# synthesizer-IF-Si4112.net
KiCad netlist of a schematic drawn in EAGLE
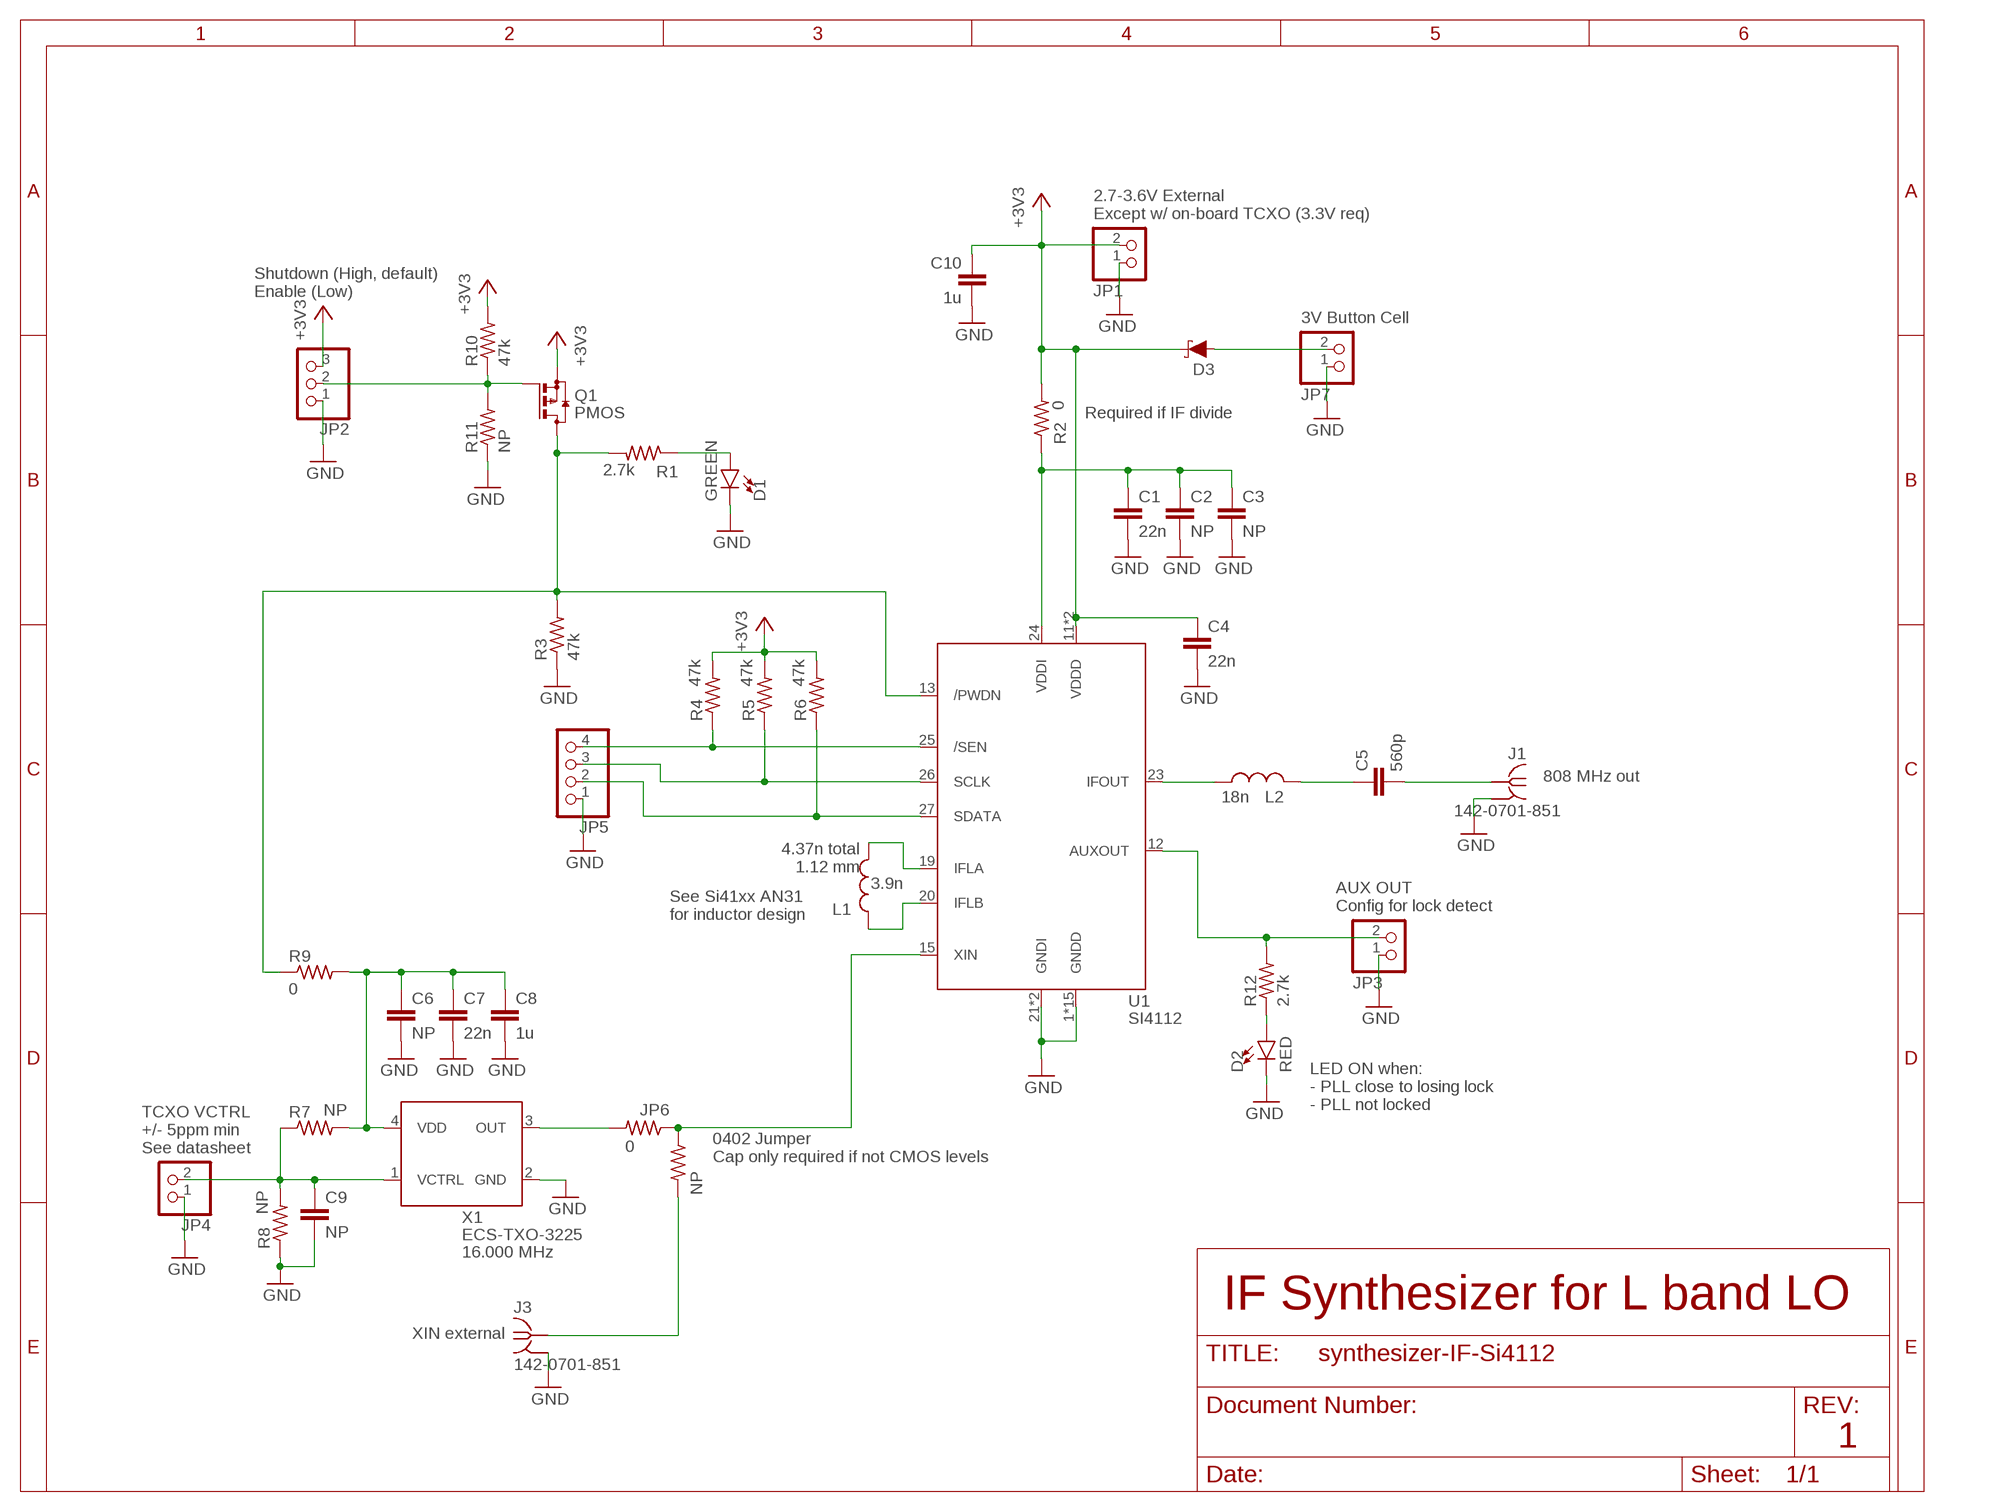
[diagram p0: schematic, sheet 1]

(export (version "E")
  (design (tool "Eeschema 10.0.6"))
  (components
    (comp (ref "C1")
      (value "22n")
      (footprint "eagle-import:.0603-B-NOSILK")
      (libsource (lib "eagle-import") (part "C-EU0603-B-NOSILK"))
    )
    (comp (ref "C2")
      (value "NP")
      (footprint "eagle-import:.0603-B-NOSILK")
      (libsource (lib "eagle-import") (part "C-EU0603-B-NOSILK"))
    )
    (comp (ref "C3")
      (value "NP")
      (footprint "eagle-import:.0603-B-NOSILK")
      (libsource (lib "eagle-import") (part "C-EU0603-B-NOSILK"))
    )
    (comp (ref "C4")
      (value "22n")
      (footprint "eagle-import:.0603-B-NOSILK")
      (libsource (lib "eagle-import") (part "C-EU0603-B-NOSILK"))
    )
    (comp (ref "C5")
      (value "560p")
      (footprint "eagle-import:.0402-B-NOSILK")
      (libsource (lib "eagle-import") (part "C-EU0402-B-NOSILK"))
    )
    (comp (ref "C6")
      (value "NP")
      (footprint "eagle-import:.0603-B-NOSILK")
      (libsource (lib "eagle-import") (part "C-EU0603-B-NOSILK"))
    )
    (comp (ref "C7")
      (value "22n")
      (footprint "eagle-import:.0603-B-NOSILK")
      (libsource (lib "eagle-import") (part "C-EU0603-B-NOSILK"))
    )
    (comp (ref "C8")
      (value "1u")
      (footprint "eagle-import:.0603-B-NOSILK")
      (libsource (lib "eagle-import") (part "C-EU0603-B-NOSILK"))
    )
    (comp (ref "C9")
      (value "NP")
      (footprint "eagle-import:.0603-B-NOSILK")
      (libsource (lib "eagle-import") (part "C-EU0603-B-NOSILK"))
    )
    (comp (ref "C10")
      (value "1u")
      (footprint "eagle-import:.0603-B-NOSILK")
      (libsource (lib "eagle-import") (part "C-EU0603-B-NOSILK"))
    )
    (comp (ref "D1")
      (value "GREEN")
      (footprint "eagle-import:LED-0603")
      (libsource (lib "eagle-import") (part "LED-GREEN0603"))
    )
    (comp (ref "D2")
      (value "RED")
      (footprint "eagle-import:LED-0603")
      (libsource (lib "eagle-import") (part "LED-GREEN0603"))
    )
    (comp (ref "D3")
      (value "120mA/40V/370mV")
      (footprint "eagle-import:SOD-523")
      (libsource (lib "eagle-import") (part "DIODE-SCHOTTKY-RB751S40"))
    )
    (comp (ref "J1")
      (value "142-0701-851")
      (footprint "eagle-import:142-0701-851")
      (libsource (lib "eagle-import") (part "142-0701-851"))
    )
    (comp (ref "J3")
      (value "142-0701-851")
      (footprint "eagle-import:142-0701-851")
      (libsource (lib "eagle-import") (part "142-0701-851"))
    )
    (comp (ref "JP1")
      (value "PINHD-1X2")
      (footprint "eagle-import:1X02")
      (libsource (lib "eagle-import") (part "PINHD-1X2"))
    )
    (comp (ref "JP2")
      (value "PINHD-1X3")
      (footprint "eagle-import:1X03")
      (libsource (lib "eagle-import") (part "PINHD-1X3"))
    )
    (comp (ref "JP3")
      (value "PINHD-1X2")
      (footprint "eagle-import:1X02")
      (libsource (lib "eagle-import") (part "PINHD-1X2"))
    )
    (comp (ref "JP4")
      (value "PINHD-1X2")
      (footprint "eagle-import:1X02")
      (libsource (lib "eagle-import") (part "PINHD-1X2"))
    )
    (comp (ref "JP5")
      (value "PINHD-1X4")
      (footprint "eagle-import:1X04")
      (libsource (lib "eagle-import") (part "PINHD-1X4"))
    )
    (comp (ref "JP6")
      (value "0")
      (footprint "eagle-import:.0402-B-NOSILK")
      (libsource (lib "eagle-import") (part "R-US_0402-B-NOSILK"))
    )
    (comp (ref "JP7")
      (value "PINHD-1X2")
      (footprint "eagle-import:1X02")
      (libsource (lib "eagle-import") (part "PINHD-1X2"))
    )
    (comp (ref "L1")
      (value "3.9n")
      (footprint "eagle-import:.0402-C-NOSILK")
      (libsource (lib "eagle-import") (part "L-US0402-C-NOSILK"))
    )
    (comp (ref "L2")
      (value "18n")
      (footprint "eagle-import:.0402-B-NOSILK")
      (libsource (lib "eagle-import") (part "L-US0402-B-NOSILK"))
    )
    (comp (ref "Q1")
      (value "PMOS")
      (footprint "eagle-import:SOT23")
      (libsource (lib "eagle-import") (part "BSS84"))
    )
    (comp (ref "R1")
      (value "2.7k")
      (footprint "eagle-import:.0603-B-NOSILK")
      (libsource (lib "eagle-import") (part "R-US_0603-B-NOSILK"))
    )
    (comp (ref "R2")
      (value "0")
      (footprint "eagle-import:.0603-B-NOSILK")
      (libsource (lib "eagle-import") (part "R-US_0603-B-NOSILK"))
    )
    (comp (ref "R3")
      (value "47k")
      (footprint "eagle-import:.0402-B-NOSILK")
      (libsource (lib "eagle-import") (part "R-US_0402-B-NOSILK"))
    )
    (comp (ref "R4")
      (value "47k")
      (footprint "eagle-import:.0402-B-NOSILK")
      (libsource (lib "eagle-import") (part "R-US_0402-B-NOSILK"))
    )
    (comp (ref "R5")
      (value "47k")
      (footprint "eagle-import:.0402-B-NOSILK")
      (libsource (lib "eagle-import") (part "R-US_0402-B-NOSILK"))
    )
    (comp (ref "R6")
      (value "47k")
      (footprint "eagle-import:.0402-B-NOSILK")
      (libsource (lib "eagle-import") (part "R-US_0402-B-NOSILK"))
    )
    (comp (ref "R7")
      (value "NP")
      (footprint "eagle-import:.0603-B-NOSILK")
      (libsource (lib "eagle-import") (part "R-US_0603-B-NOSILK"))
    )
    (comp (ref "R8")
      (value "NP")
      (footprint "eagle-import:.0603-B-NOSILK")
      (libsource (lib "eagle-import") (part "R-US_0603-B-NOSILK"))
    )
    (comp (ref "R9")
      (value "0")
      (footprint "eagle-import:.0603-B-NOSILK")
      (libsource (lib "eagle-import") (part "R-US_0603-B-NOSILK"))
    )
    (comp (ref "R10")
      (value "47k")
      (footprint "eagle-import:.0402-B-NOSILK")
      (libsource (lib "eagle-import") (part "R-US_0402-B-NOSILK"))
    )
    (comp (ref "R11")
      (value "NP")
      (footprint "eagle-import:.0402-B-NOSILK")
      (libsource (lib "eagle-import") (part "R-US_0402-B-NOSILK"))
    )
    (comp (ref "R12")
      (value "2.7k")
      (footprint "eagle-import:.0603-B-NOSILK")
      (libsource (lib "eagle-import") (part "R-US_0603-B-NOSILK"))
    )
    (comp (ref "R99")
      (value "NP")
      (footprint "eagle-import:.0402-B-NOSILK")
      (libsource (lib "eagle-import") (part "R-US_0402-B-NOSILK"))
    )
    (comp (ref "U1")
      (value "SI4112")
      (footprint "eagle-import:QFN28-5X5-WITH-CENTER-PAD")
      (libsource (lib "eagle-import") (part "SI4112"))
    )
    (comp (ref "X1")
      (value "ECS-TXO-3225")
      (footprint "eagle-import:3.2X2.5")
      (libsource (lib "eagle-import") (part "ECS-TXO-3225"))
    )
  )
  (nets
    (net (code "1") (name "+3V3") (class "Default")
      (node (ref "C10") (pin "1") (pinfunction "1_1") (pintype "passive"))
      (node (ref "C4") (pin "1") (pinfunction "1_1") (pintype "passive"))
      (node (ref "D3") (pin "C") (pinfunction "C_C") (pintype "passive"))
      (node (ref "JP1") (pin "2") (pinfunction "2_2") (pintype "passive"))
      (node (ref "JP2") (pin "3") (pinfunction "3_3") (pintype "passive"))
      (node (ref "Q1") (pin "2") (pinfunction "S_2") (pintype "passive"))
      (node (ref "R10") (pin "2") (pinfunction "2_2") (pintype "passive"))
      (node (ref "R2") (pin "2") (pinfunction "2_2") (pintype "passive"))
      (node (ref "R4") (pin "2") (pinfunction "2_2") (pintype "passive"))
      (node (ref "R5") (pin "2") (pinfunction "2_2") (pintype "passive"))
      (node (ref "R6") (pin "2") (pinfunction "2_2") (pintype "passive"))
      (node (ref "U1") (pin "11") (pinfunction "VDDD_11") (pintype "power_in"))
      (node (ref "U1") (pin "17") (pinfunction "VDDD_17") (pintype "power_in"))
    )
    (net (code "2") (name "GND") (class "Default")
      (node (ref "C1") (pin "2") (pinfunction "2_2") (pintype "passive"))
      (node (ref "C10") (pin "2") (pinfunction "2_2") (pintype "passive"))
      (node (ref "C2") (pin "2") (pinfunction "2_2") (pintype "passive"))
      (node (ref "C3") (pin "2") (pinfunction "2_2") (pintype "passive"))
      (node (ref "C4") (pin "2") (pinfunction "2_2") (pintype "passive"))
      (node (ref "C6") (pin "2") (pinfunction "2_2") (pintype "passive"))
      (node (ref "C7") (pin "2") (pinfunction "2_2") (pintype "passive"))
      (node (ref "C8") (pin "2") (pinfunction "2_2") (pintype "passive"))
      (node (ref "C9") (pin "2") (pinfunction "2_2") (pintype "passive"))
      (node (ref "D1") (pin "C") (pinfunction "C_C") (pintype "passive"))
      (node (ref "D2") (pin "C") (pinfunction "C_C") (pintype "passive"))
      (node (ref "J1") (pin "GND1") (pinfunction "GND_GND1") (pintype "bidirectional"))
      (node (ref "J1") (pin "GND2") (pinfunction "GND_GND2") (pintype "bidirectional"))
      (node (ref "J1") (pin "GND3") (pinfunction "GND_GND3") (pintype "bidirectional"))
      (node (ref "J1") (pin "GND4") (pinfunction "GND_GND4") (pintype "bidirectional"))
      (node (ref "J3") (pin "GND1") (pinfunction "GND_GND1") (pintype "bidirectional"))
      (node (ref "J3") (pin "GND2") (pinfunction "GND_GND2") (pintype "bidirectional"))
      (node (ref "J3") (pin "GND3") (pinfunction "GND_GND3") (pintype "bidirectional"))
      (node (ref "J3") (pin "GND4") (pinfunction "GND_GND4") (pintype "bidirectional"))
      (node (ref "JP1") (pin "1") (pinfunction "1_1") (pintype "passive"))
      (node (ref "JP2") (pin "1") (pinfunction "1_1") (pintype "passive"))
      (node (ref "JP3") (pin "1") (pinfunction "1_1") (pintype "passive"))
      (node (ref "JP4") (pin "1") (pinfunction "1_1") (pintype "passive"))
      (node (ref "JP5") (pin "1") (pinfunction "1_1") (pintype "passive"))
      (node (ref "JP7") (pin "1") (pinfunction "1_1") (pintype "passive"))
      (node (ref "R11") (pin "1") (pinfunction "1_1") (pintype "passive"))
      (node (ref "R3") (pin "1") (pinfunction "1_1") (pintype "passive"))
      (node (ref "R8") (pin "1") (pinfunction "1_1") (pintype "passive"))
      (node (ref "U1") (pin "1") (pinfunction "GNDD_1") (pintype "power_in"))
      (node (ref "U1") (pin "10") (pinfunction "GNDD_10") (pintype "power_in"))
      (node (ref "U1") (pin "14") (pinfunction "GNDD_14") (pintype "power_in"))
      (node (ref "U1") (pin "16") (pinfunction "GNDD_16") (pintype "power_in"))
      (node (ref "U1") (pin "18") (pinfunction "GNDD_18") (pintype "power_in"))
      (node (ref "U1") (pin "2") (pinfunction "GNDD_2") (pintype "power_in"))
      (node (ref "U1") (pin "21") (pinfunction "GNDI_21") (pintype "power_in"))
      (node (ref "U1") (pin "22") (pinfunction "GNDI_22") (pintype "power_in"))
      (node (ref "U1") (pin "28") (pinfunction "GNDD_28") (pintype "power_in"))
      (node (ref "U1") (pin "3") (pinfunction "GNDD_3") (pintype "power_in"))
      (node (ref "U1") (pin "4") (pinfunction "GNDD_4") (pintype "power_in"))
      (node (ref "U1") (pin "5") (pinfunction "GNDD_5") (pintype "power_in"))
      (node (ref "U1") (pin "6") (pinfunction "GNDD_6") (pintype "power_in"))
      (node (ref "U1") (pin "7") (pinfunction "GNDD_7") (pintype "power_in"))
      (node (ref "U1") (pin "8") (pinfunction "GNDD_8") (pintype "power_in"))
      (node (ref "U1") (pin "9") (pinfunction "GNDD_9") (pintype "power_in"))
      (node (ref "U1") (pin "PAD") (pinfunction "GNDD_PAD") (pintype "power_in"))
      (node (ref "X1") (pin "2") (pinfunction "GND_2") (pintype "power_in"))
    )
    (net (code "3") (name "Net-(C5-Pad1)") (class "Default")
      (node (ref "C5") (pin "1") (pinfunction "1_1") (pintype "passive"))
      (node (ref "L2") (pin "2") (pinfunction "2_2") (pintype "passive"))
    )
    (net (code "4") (name "Net-(D1-PadA)") (class "Default")
      (node (ref "D1") (pin "A") (pinfunction "A_A") (pintype "passive"))
      (node (ref "R1") (pin "1") (pinfunction "1_1") (pintype "passive"))
    )
    (net (code "5") (name "Net-(D2-PadA)") (class "Default")
      (node (ref "D2") (pin "A") (pinfunction "A_A") (pintype "passive"))
      (node (ref "R12") (pin "1") (pinfunction "1_1") (pintype "passive"))
    )
    (net (code "6") (name "Net-(D3-PadA)") (class "Default")
      (node (ref "D3") (pin "A") (pinfunction "A_A") (pintype "passive"))
      (node (ref "JP7") (pin "2") (pinfunction "2_2") (pintype "passive"))
    )
    (net (code "7") (name "Net-(J1-RF)") (class "Default")
      (node (ref "C5") (pin "2") (pinfunction "2_2") (pintype "passive"))
      (node (ref "J1") (pin "RF1") (pinfunction "RF_RF1") (pintype "bidirectional"))
    )
    (net (code "8") (name "Net-(J3-RF)") (class "Default")
      (node (ref "J3") (pin "RF1") (pinfunction "RF_RF1") (pintype "bidirectional"))
      (node (ref "R99") (pin "2") (pinfunction "2_2") (pintype "passive"))
    )
    (net (code "9") (name "Net-(Q1-D)") (class "Default")
      (node (ref "Q1") (pin "3") (pinfunction "D_3") (pintype "passive"))
      (node (ref "R1") (pin "2") (pinfunction "2_2") (pintype "passive"))
      (node (ref "R3") (pin "2") (pinfunction "2_2") (pintype "passive"))
      (node (ref "R9") (pin "1") (pinfunction "1_1") (pintype "passive"))
      (node (ref "U1") (pin "13") (pinfunction "/PWDN_13") (pintype "input"))
    )
    (net (code "10") (name "Net-(Q1-G)") (class "Default")
      (node (ref "JP2") (pin "2") (pinfunction "2_2") (pintype "passive"))
      (node (ref "Q1") (pin "1") (pinfunction "G_1") (pintype "passive"))
      (node (ref "R10") (pin "1") (pinfunction "1_1") (pintype "passive"))
      (node (ref "R11") (pin "2") (pinfunction "2_2") (pintype "passive"))
    )
    (net (code "11") (name "Net-(U1-AUXOUT)") (class "Default")
      (node (ref "JP3") (pin "2") (pinfunction "2_2") (pintype "passive"))
      (node (ref "R12") (pin "2") (pinfunction "2_2") (pintype "passive"))
      (node (ref "U1") (pin "12") (pinfunction "AUXOUT_12") (pintype "output"))
    )
    (net (code "12") (name "Net-(U1-IFLA)") (class "Default")
      (node (ref "L1") (pin "2") (pinfunction "2_2") (pintype "passive"))
      (node (ref "U1") (pin "19") (pinfunction "IFLA_19") (pintype "input"))
    )
    (net (code "13") (name "Net-(U1-IFLB)") (class "Default")
      (node (ref "L1") (pin "1") (pinfunction "1_1") (pintype "passive"))
      (node (ref "U1") (pin "20") (pinfunction "IFLB_20") (pintype "input"))
    )
    (net (code "14") (name "Net-(U1-IFOUT)") (class "Default")
      (node (ref "L2") (pin "1") (pinfunction "1_1") (pintype "passive"))
      (node (ref "U1") (pin "23") (pinfunction "IFOUT_23") (pintype "output"))
    )
    (net (code "15") (name "Net-(U1-SCLK)") (class "Default")
      (node (ref "JP5") (pin "3") (pinfunction "3_3") (pintype "passive"))
      (node (ref "R5") (pin "1") (pinfunction "1_1") (pintype "passive"))
      (node (ref "U1") (pin "26") (pinfunction "SCLK_26") (pintype "input"))
    )
    (net (code "16") (name "Net-(U1-SDATA)") (class "Default")
      (node (ref "JP5") (pin "2") (pinfunction "2_2") (pintype "passive"))
      (node (ref "R6") (pin "1") (pinfunction "1_1") (pintype "passive"))
      (node (ref "U1") (pin "27") (pinfunction "SDATA_27") (pintype "input"))
    )
    (net (code "17") (name "Net-(U1-VDDI)") (class "Default")
      (node (ref "C1") (pin "1") (pinfunction "1_1") (pintype "passive"))
      (node (ref "C2") (pin "1") (pinfunction "1_1") (pintype "passive"))
      (node (ref "C3") (pin "1") (pinfunction "1_1") (pintype "passive"))
      (node (ref "R2") (pin "1") (pinfunction "1_1") (pintype "passive"))
      (node (ref "U1") (pin "24") (pinfunction "VDDI_24") (pintype "power_in"))
    )
    (net (code "18") (name "Net-(U1-XIN)") (class "Default")
      (node (ref "JP6") (pin "1") (pinfunction "1_1") (pintype "passive"))
      (node (ref "R99") (pin "1") (pinfunction "1_1") (pintype "passive"))
      (node (ref "U1") (pin "15") (pinfunction "XIN_15") (pintype "input"))
    )
    (net (code "19") (name "Net-(U1-{slash}SEN)") (class "Default")
      (node (ref "JP5") (pin "4") (pinfunction "4_4") (pintype "passive"))
      (node (ref "R4") (pin "1") (pinfunction "1_1") (pintype "passive"))
      (node (ref "U1") (pin "25") (pinfunction "/SEN_25") (pintype "input"))
    )
    (net (code "20") (name "Net-(X1-OUT)") (class "Default")
      (node (ref "JP6") (pin "2") (pinfunction "2_2") (pintype "passive"))
      (node (ref "X1") (pin "3") (pinfunction "OUT_3") (pintype "output"))
    )
    (net (code "21") (name "Net-(X1-VCTRL)") (class "Default")
      (node (ref "C9") (pin "1") (pinfunction "1_1") (pintype "passive"))
      (node (ref "JP4") (pin "2") (pinfunction "2_2") (pintype "passive"))
      (node (ref "R7") (pin "1") (pinfunction "1_1") (pintype "passive"))
      (node (ref "R8") (pin "2") (pinfunction "2_2") (pintype "passive"))
      (node (ref "X1") (pin "1") (pinfunction "VCTRL_1") (pintype "input"))
    )
    (net (code "22") (name "Net-(X1-VDD)") (class "Default")
      (node (ref "C6") (pin "1") (pinfunction "1_1") (pintype "passive"))
      (node (ref "C7") (pin "1") (pinfunction "1_1") (pintype "passive"))
      (node (ref "C8") (pin "1") (pinfunction "1_1") (pintype "passive"))
      (node (ref "R7") (pin "2") (pinfunction "2_2") (pintype "passive"))
      (node (ref "R9") (pin "2") (pinfunction "2_2") (pintype "passive"))
      (node (ref "X1") (pin "4") (pinfunction "VDD_4") (pintype "power_in"))
    )
  )
)
